# LampBoard.net
KiCad netlist of a schematic drawn in EAGLE
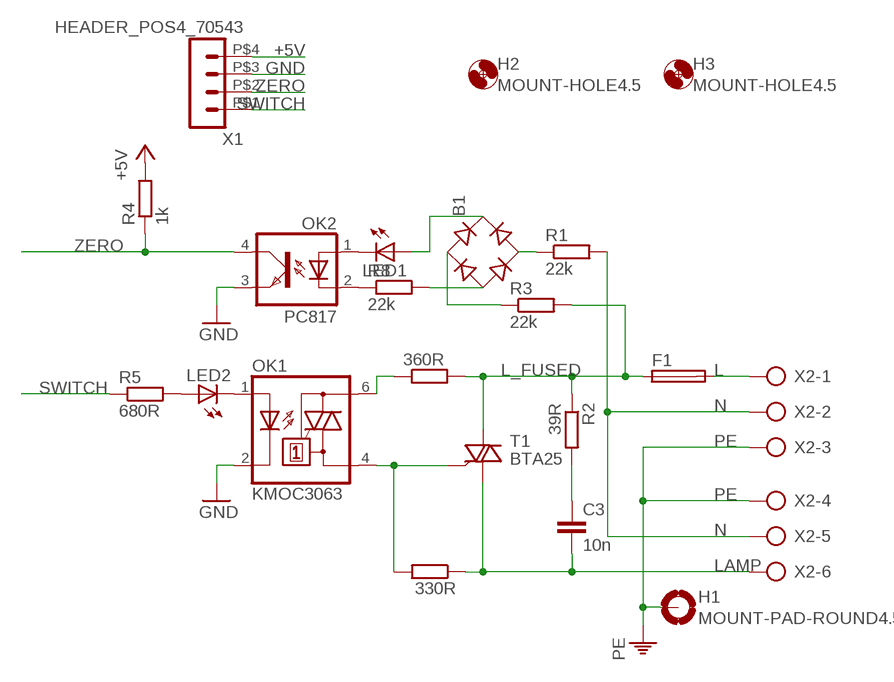
[diagram p0: schematic, sheet 1]

(export (version "E")
  (design (tool "Eeschema 10.0.6"))
  (components
    (comp (ref "330R")
      (value "R-EU_0411/12")
      (footprint "eagle-import:0411_12")
      (libsource (lib "eagle-import") (part "R-EU_0411/12"))
    )
    (comp (ref "360R")
      (value "R-EU_0411/12")
      (footprint "eagle-import:0411_12")
      (libsource (lib "eagle-import") (part "R-EU_0411/12"))
    )
    (comp (ref "B1")
      (value "B-DIL")
      (footprint "eagle-import:B-DIL")
      (libsource (lib "eagle-import") (part "B-DIL"))
    )
    (comp (ref "C3")
      (value "10n")
      (footprint "eagle-import:C050-045X075")
      (libsource (lib "eagle-import") (part "C-EU050-045X075"))
    )
    (comp (ref "F1")
      (value "SH22,5A")
      (footprint "eagle-import:SH22,5A")
      (fields (field (name "MPN") "0031.7701.11"))
      (libsource (lib "eagle-import") (part "SH22,5A"))
    )
    (comp (ref "H1")
      (value "MOUNT-PAD-ROUND4.5")
      (footprint "eagle-import:4,5-PAD")
      (libsource (lib "eagle-import") (part "MOUNT-PAD-ROUND4.5"))
    )
    (comp (ref "H2")
      (value "MOUNT-HOLE4.5")
      (footprint "eagle-import:4,5")
      (libsource (lib "eagle-import") (part "MOUNT-HOLE4.5"))
    )
    (comp (ref "H3")
      (value "MOUNT-HOLE4.5")
      (footprint "eagle-import:4,5")
      (libsource (lib "eagle-import") (part "MOUNT-HOLE4.5"))
    )
    (comp (ref "LED1")
      (value "LED3MM")
      (footprint "eagle-import:LED3MM")
      (libsource (lib "eagle-import") (part "LED3MM"))
    )
    (comp (ref "LED2")
      (value "LED3MM")
      (footprint "eagle-import:LED3MM")
      (libsource (lib "eagle-import") (part "LED3MM"))
    )
    (comp (ref "OK1")
      (value "KMOC3063")
      (footprint "eagle-import:DIL06")
      (fields (field (name "MF") "FAIRCHILD SEMICONDUCTOR") (field (name "MPN") "MOC3041M"))
      (libsource (lib "eagle-import") (part "MOC3041M"))
    )
    (comp (ref "OK2")
      (value "PC817")
      (footprint "eagle-import:DIL04")
      (fields (field (name "MPN") "PC817X4J000F"))
      (libsource (lib "eagle-import") (part "PC817"))
    )
    (comp (ref "R1")
      (value "22k")
      (footprint "eagle-import:0207_10")
      (libsource (lib "eagle-import") (part "R-EU_0207/10"))
    )
    (comp (ref "R2")
      (value "39R")
      (footprint "eagle-import:0411_12")
      (libsource (lib "eagle-import") (part "R-EU_0411/12"))
    )
    (comp (ref "R3")
      (value "22k")
      (footprint "eagle-import:0207_10")
      (libsource (lib "eagle-import") (part "R-EU_0207/10"))
    )
    (comp (ref "R4")
      (value "1k")
      (footprint "eagle-import:M0805")
      (libsource (lib "eagle-import") (part "R-EU_M0805"))
    )
    (comp (ref "R5")
      (value "680R")
      (footprint "eagle-import:M0805")
      (libsource (lib "eagle-import") (part "R-EU_M0805"))
    )
    (comp (ref "R8")
      (value "22k")
      (footprint "eagle-import:0207_10")
      (libsource (lib "eagle-import") (part "R-EU_0207/10"))
    )
    (comp (ref "T1")
      (value "BTA25")
      (footprint "eagle-import:TO220BV")
      (libsource (lib "eagle-import") (part "BT138-V"))
    )
    (comp (ref "X1")
      (value "HEADER_POS4_70543")
      (footprint "eagle-import:70543-POS4")
      (libsource (lib "eagle-import") (part "HEADER_POS4_?70543"))
    )
    (comp (ref "X2")
      (value "AK300/6")
      (footprint "eagle-import:AK300_6")
      (libsource (lib "eagle-import") (part "AK300/6"))
    )
  )
  (nets
    (net (code "1") (name "+5V") (class "Default")
      (node (ref "R4") (pin "2") (pinfunction "2_2") (pintype "passive"))
      (node (ref "X1") (pin "P$4") (pinfunction "4_P$4") (pintype "passive"))
    )
    (net (code "2") (name "/L") (class "Default")
      (node (ref "F1") (pin "2") (pinfunction "2_2") (pintype "passive"))
      (node (ref "X2") (pin "1") (pinfunction "KL_1") (pintype "passive"))
    )
    (net (code "3") (name "/LAMP") (class "Default")
      (node (ref "330R") (pin "1") (pinfunction "1_1") (pintype "passive"))
      (node (ref "C3") (pin "2") (pinfunction "2_2") (pintype "passive"))
      (node (ref "T1") (pin "T1") (pinfunction "A1_T1") (pintype "passive"))
      (node (ref "X2") (pin "6") (pinfunction "KL_6") (pintype "passive"))
    )
    (net (code "4") (name "/L_FUSED") (class "Default")
      (node (ref "360R") (pin "2") (pinfunction "2_2") (pintype "passive"))
      (node (ref "F1") (pin "1") (pinfunction "1_1") (pintype "passive"))
      (node (ref "R2") (pin "1") (pinfunction "1_1") (pintype "passive"))
      (node (ref "R3") (pin "2") (pinfunction "2_2") (pintype "passive"))
      (node (ref "T1") (pin "T2") (pinfunction "A2_T2") (pintype "passive"))
    )
    (net (code "5") (name "/N") (class "Default")
      (node (ref "R1") (pin "2") (pinfunction "2_2") (pintype "passive"))
      (node (ref "X2") (pin "2") (pinfunction "KL_2") (pintype "passive"))
      (node (ref "X2") (pin "5") (pinfunction "KL_5") (pintype "passive"))
    )
    (net (code "6") (name "/SWITCH") (class "Default")
      (node (ref "R5") (pin "1") (pinfunction "1_1") (pintype "passive"))
      (node (ref "X1") (pin "P$1") (pinfunction "1_P$1") (pintype "passive"))
    )
    (net (code "7") (name "/ZERO") (class "Default")
      (node (ref "OK2") (pin "4") (pinfunction "COL_4") (pintype "passive"))
      (node (ref "R4") (pin "1") (pinfunction "1_1") (pintype "passive"))
      (node (ref "X1") (pin "P$2") (pinfunction "2_P$2") (pintype "passive"))
    )
    (net (code "8") (name "GND") (class "Default")
      (node (ref "OK1") (pin "2") (pinfunction "C_2") (pintype "passive"))
      (node (ref "OK2") (pin "3") (pinfunction "EMIT_3") (pintype "passive"))
      (node (ref "X1") (pin "P$3") (pinfunction "3_P$3") (pintype "passive"))
    )
    (net (code "9") (name "Net-(B1-Pad+)") (class "Default")
      (node (ref "B1") (pin "+") (pinfunction "+_+") (pintype "passive"))
      (node (ref "LED1") (pin "A") (pinfunction "A_A") (pintype "passive"))
    )
    (net (code "10") (name "Net-(B1-Pad-)") (class "Default")
      (node (ref "B1") (pin "-") (pinfunction "-_-") (pintype "passive"))
      (node (ref "R8") (pin "2") (pinfunction "2_2") (pintype "passive"))
    )
    (net (code "11") (name "Net-(B1-PadAC1)") (class "Default")
      (node (ref "B1") (pin "AC1") (pinfunction "AC1_AC1") (pintype "passive"))
      (node (ref "R3") (pin "1") (pinfunction "1_1") (pintype "passive"))
    )
    (net (code "12") (name "Net-(B1-PadAC2)") (class "Default")
      (node (ref "B1") (pin "AC2") (pinfunction "AC2_AC2") (pintype "passive"))
      (node (ref "R1") (pin "1") (pinfunction "1_1") (pintype "passive"))
    )
    (net (code "13") (name "Net-(C3-Pad1)") (class "Default")
      (node (ref "C3") (pin "1") (pinfunction "1_1") (pintype "passive"))
      (node (ref "R2") (pin "2") (pinfunction "2_2") (pintype "passive"))
    )
    (net (code "14") (name "Net-(LED1-C)") (class "Default")
      (node (ref "LED1") (pin "K") (pinfunction "C_K") (pintype "passive"))
      (node (ref "OK2") (pin "1") (pinfunction "A_1") (pintype "passive"))
    )
    (net (code "15") (name "Net-(LED2-C)") (class "Default")
      (node (ref "LED2") (pin "K") (pinfunction "C_K") (pintype "passive"))
      (node (ref "OK1") (pin "1") (pinfunction "A_1") (pintype "passive"))
    )
    (net (code "16") (name "Net-(LED2-PadA)") (class "Default")
      (node (ref "LED2") (pin "A") (pinfunction "A_A") (pintype "passive"))
      (node (ref "R5") (pin "2") (pinfunction "2_2") (pintype "passive"))
    )
    (net (code "17") (name "Net-(OK1-A1)") (class "Default")
      (node (ref "330R") (pin "2") (pinfunction "2_2") (pintype "passive"))
      (node (ref "OK1") (pin "4") (pinfunction "A1_4") (pintype "passive"))
      (node (ref "T1") (pin "G") (pinfunction "G_G") (pintype "passive"))
    )
    (net (code "18") (name "Net-(OK1-A2)") (class "Default")
      (node (ref "360R") (pin "1") (pinfunction "1_1") (pintype "passive"))
      (node (ref "OK1") (pin "6") (pinfunction "A2_6") (pintype "passive"))
    )
    (net (code "19") (name "Net-(OK2-C)") (class "Default")
      (node (ref "OK2") (pin "2") (pinfunction "C_2") (pintype "passive"))
      (node (ref "R8") (pin "1") (pinfunction "1_1") (pintype "passive"))
    )
    (net (code "20") (name "PE") (class "Default")
      (node (ref "H1") (pin "B4,5") (pinfunction "MOUNT_B4,5") (pintype "passive"))
      (node (ref "X2") (pin "3") (pinfunction "KL_3") (pintype "passive"))
      (node (ref "X2") (pin "4") (pinfunction "KL_4") (pintype "passive"))
    )
  )
)
